# TPS54531.net
KiCad netlist of a schematic drawn in Altium Designer
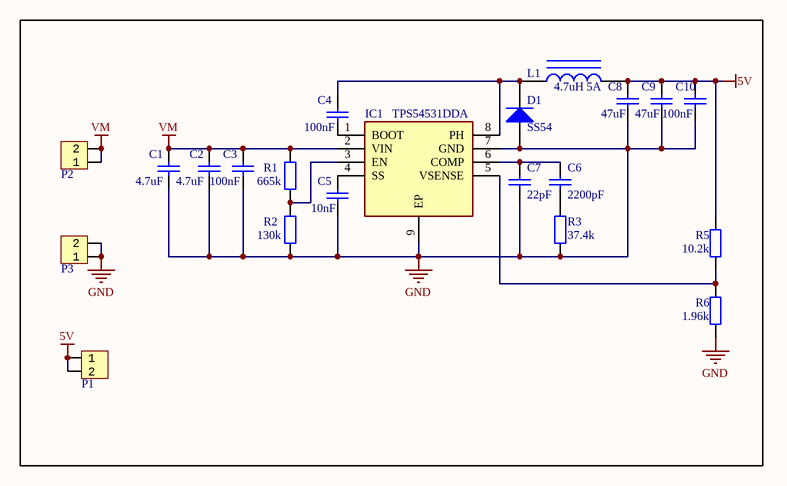
[diagram p0: TPS54531.SchDoc]

(export (version "E")
  (design (tool "Eeschema 10.0.6"))
  (components
    (comp (ref "C1")
      (value "4.7uF")
      (footprint "CAP-0603")
      (description "贴片电容")
      (libsource (lib "Power_Lib_Altium") (part "CAP"))
    )
    (comp (ref "C2")
      (value "4.7uF")
      (footprint "CAP-0603")
      (description "贴片电容")
      (libsource (lib "Power_Lib_Altium") (part "CAP"))
    )
    (comp (ref "C3")
      (value "100nF")
      (footprint "CAP-0603")
      (description "贴片电容")
      (libsource (lib "Power_Lib_Altium") (part "CAP"))
    )
    (comp (ref "C4")
      (value "100nF")
      (footprint "CAP-0603")
      (description "贴片电容")
      (libsource (lib "Power_Lib_Altium") (part "CAP"))
    )
    (comp (ref "C5")
      (value "10nF")
      (footprint "CAP-0603")
      (description "贴片电容")
      (libsource (lib "Power_Lib_Altium") (part "CAP"))
    )
    (comp (ref "C6")
      (value "2200pF")
      (footprint "CAP-0603")
      (description "贴片电容")
      (libsource (lib "Power_Lib_Altium") (part "CAP"))
    )
    (comp (ref "C7")
      (value "22pF")
      (footprint "CAP-0603")
      (description "贴片电容")
      (libsource (lib "Power_Lib_Altium") (part "CAP"))
    )
    (comp (ref "C8")
      (value "47uF")
      (footprint "CAP-0603")
      (description "贴片电容")
      (libsource (lib "Power_Lib_Altium") (part "CAP"))
    )
    (comp (ref "C9")
      (value "47uF")
      (footprint "CAP-0603")
      (description "贴片电容")
      (libsource (lib "Power_Lib_Altium") (part "CAP"))
    )
    (comp (ref "C10")
      (value "100nF")
      (footprint "CAP-0603")
      (description "贴片电容")
      (libsource (lib "Power_Lib_Altium") (part "CAP"))
    )
    (comp (ref "D1")
      (value "SS54")
      (footprint "SOD_123")
      (description "肖特基二极管")
      (libsource (lib "Power_Lib_Altium") (part "DIODE"))
    )
    (comp (ref "IC1")
      (value "TPS54531DDA")
      (footprint "SOIC_8_PAD")
      (description "集成稳压芯片")
      (fields (field (name "MOUSER PART NUMBER") "595-TPS54531DDA"))
      (libsource (lib "Power_Lib_Altium") (part "TPS54531DDA"))
    )
    (comp (ref "L1")
      (value "4.7uH 5A")
      (footprint "L-10040")
      (description "电感")
      (libsource (lib "Power_Lib_Altium") (part "INDUCTOR"))
    )
    (comp (ref "P1")
      (value "HDR1x2_2.54")
      (footprint "HDR1X2_2.54_180")
      (description "Header")
      (libsource (lib "") (part "HDR1x2_2.54_1"))
    )
    (comp (ref "P2")
      (value "HDR1x2_2.54")
      (footprint "HDR1X2_2.54_180")
      (description "Header")
      (libsource (lib "Power_Lib_Altium") (part "HDR1x2_2.54"))
    )
    (comp (ref "P3")
      (value "HDR1x2_2.54")
      (footprint "HDR1X2_2.54_180")
      (description "Header")
      (libsource (lib "Power_Lib_Altium") (part "HDR1x2_2.54"))
    )
    (comp (ref "R1")
      (value "665k")
      (footprint "R-0603")
      (description "贴片电阻")
      (libsource (lib "Power_Lib_Altium") (part "RES"))
    )
    (comp (ref "R2")
      (value "130k")
      (footprint "R-0603")
      (description "贴片电阻")
      (libsource (lib "Power_Lib_Altium") (part "RES"))
    )
    (comp (ref "R3")
      (value "37.4k")
      (footprint "R-0603")
      (description "贴片电阻")
      (libsource (lib "Power_Lib_Altium") (part "RES"))
    )
    (comp (ref "R5")
      (value "10.2k")
      (footprint "R-0603")
      (description "贴片电阻")
      (libsource (lib "Power_Lib_Altium") (part "RES"))
    )
    (comp (ref "R6")
      (value "1.96k")
      (footprint "R-0603")
      (description "贴片电阻")
      (libsource (lib "Power_Lib_Altium") (part "RES"))
    )
  )
  (nets
    (net (code "1") (name "5V") (class "Default")
      (node (ref "C10") (pin "2") (pinfunction "2_2") (pintype "passive"))
      (node (ref "C8") (pin "2") (pinfunction "2_2") (pintype "passive"))
      (node (ref "C9") (pin "2") (pinfunction "2_2") (pintype "passive"))
      (node (ref "L1") (pin "2") (pinfunction "2_2") (pintype "passive"))
      (node (ref "P1") (pin "1") (pinfunction "1_1") (pintype "passive"))
      (node (ref "P1") (pin "2") (pinfunction "2_2") (pintype "passive"))
      (node (ref "R5") (pin "2") (pinfunction "2_2") (pintype "passive"))
    )
    (net (code "2") (name "GND") (class "Default")
      (node (ref "C1") (pin "1") (pinfunction "1_1") (pintype "passive"))
      (node (ref "C10") (pin "1") (pinfunction "1_1") (pintype "passive"))
      (node (ref "C2") (pin "1") (pinfunction "1_1") (pintype "passive"))
      (node (ref "C3") (pin "1") (pinfunction "1_1") (pintype "passive"))
      (node (ref "C5") (pin "1") (pinfunction "1_1") (pintype "passive"))
      (node (ref "C7") (pin "1") (pinfunction "1_1") (pintype "passive"))
      (node (ref "C8") (pin "1") (pinfunction "1_1") (pintype "passive"))
      (node (ref "C9") (pin "1") (pinfunction "1_1") (pintype "passive"))
      (node (ref "D1") (pin "1") (pinfunction "A_1") (pintype "passive"))
      (node (ref "IC1") (pin "7") (pinfunction "GND_7") (pintype "passive"))
      (node (ref "IC1") (pin "9") (pinfunction "EP_9") (pintype "passive"))
      (node (ref "P3") (pin "1") (pinfunction "1_1") (pintype "passive"))
      (node (ref "P3") (pin "2") (pinfunction "2_2") (pintype "passive"))
      (node (ref "R2") (pin "1") (pinfunction "1_1") (pintype "passive"))
      (node (ref "R3") (pin "1") (pinfunction "1_1") (pintype "passive"))
      (node (ref "R6") (pin "1") (pinfunction "1_1") (pintype "passive"))
    )
    (net (code "3") (name "Net-(C6-Pad1)") (class "Default")
      (node (ref "C6") (pin "1") (pinfunction "1_1") (pintype "passive"))
      (node (ref "R3") (pin "2") (pinfunction "2_2") (pintype "passive"))
    )
    (net (code "4") (name "Net-(D1-K)") (class "Default")
      (node (ref "C4") (pin "2") (pinfunction "2_2") (pintype "passive"))
      (node (ref "D1") (pin "2") (pinfunction "K_2") (pintype "passive"))
      (node (ref "IC1") (pin "8") (pinfunction "PH_8") (pintype "passive"))
      (node (ref "L1") (pin "1") (pinfunction "1_1") (pintype "passive"))
    )
    (net (code "5") (name "Net-(IC1-BOOT)") (class "Default")
      (node (ref "C4") (pin "1") (pinfunction "1_1") (pintype "passive"))
      (node (ref "IC1") (pin "1") (pinfunction "BOOT_1") (pintype "passive"))
    )
    (net (code "6") (name "Net-(IC1-COMP)") (class "Default")
      (node (ref "C6") (pin "2") (pinfunction "2_2") (pintype "passive"))
      (node (ref "C7") (pin "2") (pinfunction "2_2") (pintype "passive"))
      (node (ref "IC1") (pin "6") (pinfunction "COMP_6") (pintype "passive"))
    )
    (net (code "7") (name "Net-(IC1-EN)") (class "Default")
      (node (ref "IC1") (pin "3") (pinfunction "EN_3") (pintype "passive"))
      (node (ref "R1") (pin "1") (pinfunction "1_1") (pintype "passive"))
      (node (ref "R2") (pin "2") (pinfunction "2_2") (pintype "passive"))
    )
    (net (code "8") (name "Net-(IC1-SS)") (class "Default")
      (node (ref "C5") (pin "2") (pinfunction "2_2") (pintype "passive"))
      (node (ref "IC1") (pin "4") (pinfunction "SS_4") (pintype "passive"))
    )
    (net (code "9") (name "Net-(IC1-VSENSE)") (class "Default")
      (node (ref "IC1") (pin "5") (pinfunction "VSENSE_5") (pintype "passive"))
      (node (ref "R5") (pin "1") (pinfunction "1_1") (pintype "passive"))
      (node (ref "R6") (pin "2") (pinfunction "2_2") (pintype "passive"))
    )
    (net (code "10") (name "VM") (class "Default")
      (node (ref "C1") (pin "2") (pinfunction "2_2") (pintype "passive"))
      (node (ref "C2") (pin "2") (pinfunction "2_2") (pintype "passive"))
      (node (ref "C3") (pin "2") (pinfunction "2_2") (pintype "passive"))
      (node (ref "IC1") (pin "2") (pinfunction "VIN_2") (pintype "passive"))
      (node (ref "P2") (pin "1") (pinfunction "1_1") (pintype "passive"))
      (node (ref "P2") (pin "2") (pinfunction "2_2") (pintype "passive"))
      (node (ref "R1") (pin "2") (pinfunction "2_2") (pintype "passive"))
    )
  )
)
